# Power_Supply_1.net
KiCad netlist of a schematic drawn in Altium Designer
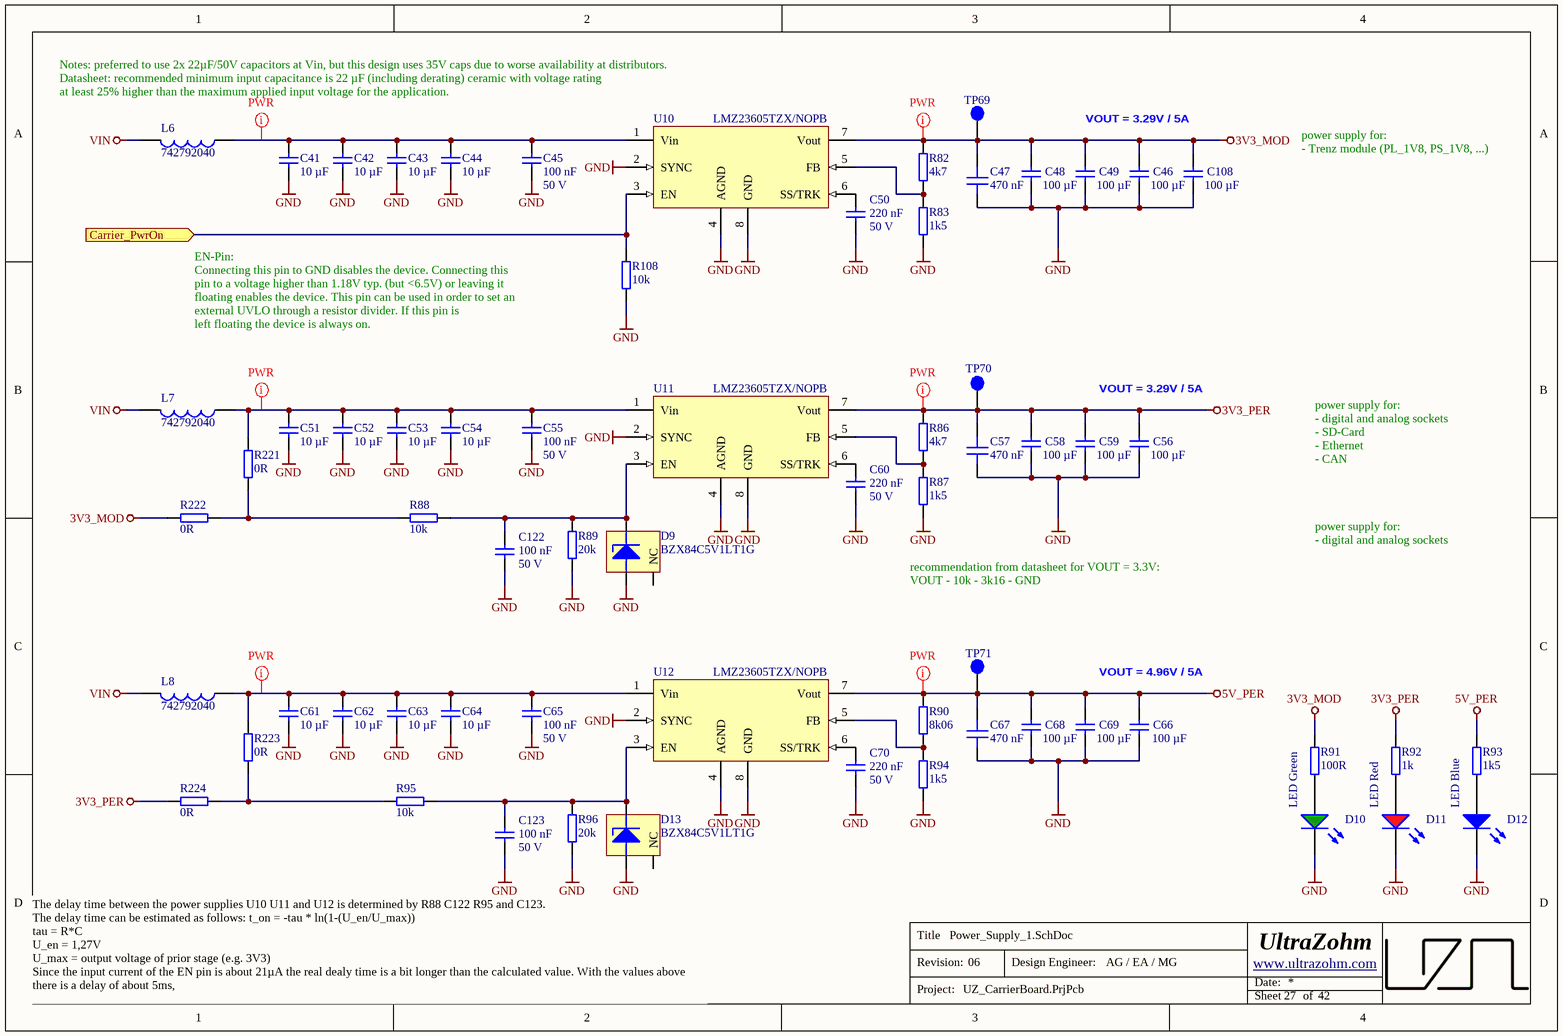
[diagram p0: Power_Supply_1.SchDoc]

(export (version "E")
  (design (tool "Eeschema 10.0.6"))
  (components
    (comp (ref "C41")
      (value "10 µF")
      (footprint "C_1206_TE")
      (description "Generic capacitor")
      (fields
        (field (name "TOLERANCE") "10 %")
        (field (name "MANUFACTURER PART NUMBER") "UZgen_C_1206_10uF_50V_X7R")
        (field (name "CREATED FROM") "MGeier")
      )
      (libsource (lib "user") (part "CAP-NP"))
    )
    (comp (ref "C42")
      (value "10 µF")
      (footprint "C_1206_TE")
      (description "Generic capacitor")
      (fields
        (field (name "TOLERANCE") "10 %")
        (field (name "MANUFACTURER PART NUMBER") "UZgen_C_1206_10uF_50V_X7R")
        (field (name "CREATED FROM") "MGeier")
      )
      (libsource (lib "user") (part "CAP-NP"))
    )
    (comp (ref "C43")
      (value "10 µF")
      (footprint "C_1206_TE")
      (description "Generic capacitor")
      (fields
        (field (name "TOLERANCE") "10 %")
        (field (name "MANUFACTURER PART NUMBER") "UZgen_C_1206_10uF_50V_X7R")
        (field (name "CREATED FROM") "MGeier")
      )
      (libsource (lib "user") (part "CAP-NP"))
    )
    (comp (ref "C44")
      (value "10 µF")
      (footprint "C_1206_TE")
      (description "Generic capacitor")
      (fields
        (field (name "TOLERANCE") "10 %")
        (field (name "MANUFACTURER PART NUMBER") "UZgen_C_1206_10uF_50V_X7R")
        (field (name "CREATED FROM") "MGeier")
      )
      (libsource (lib "user") (part "CAP-NP"))
    )
    (comp (ref "C45")
      (value "100 nF")
      (footprint "C_0603_TE")
      (description "Generic capacitor")
      (fields
        (field (name "TOLERANCE") "10 %")
        (field (name "VOLTAGE") "50 V")
        (field (name "MANUFACTURER PART NUMBER") "UZgen_C_0603_100nF_50V_X7R")
        (field (name "CREATED FROM") "AGeiger")
      )
      (libsource (lib "user") (part "CAP-NP"))
    )
    (comp (ref "C46")
      (value "100 µF")
      (footprint "C_1206_TE")
      (description "6.3V 100uF X5R ±20% 1206 Multilayer Ceramic Capacitors MLCC")
      (fields
        (field (name "TOLERANCE") "20%")
        (field (name "MANUFACTURER PART NUMBER") "CL31A107MQHNNNE")
        (field (name "CREATED FROM") "MGeier")
      )
      (libsource (lib "user") (part "CAP-NP"))
    )
    (comp (ref "C47")
      (value "470 nF")
      (footprint "C_0603_TE")
      (description "Capacitor 0603, 50 VDC, 470 nF, X5R")
      (fields
        (field (name "MANUFACTURER PART NUMBER") "CL10A474KB8NNNC")
        (field (name "MANUFACTURER") "Samsung Electro-Mechanics")
        (field (name "CREATED FROM") "AGeiger")
      )
      (libsource (lib "user") (part "Capacitor"))
    )
    (comp (ref "C48")
      (value "100 µF")
      (footprint "C_1206_TE")
      (description "6.3V 100uF X5R ±20% 1206 Multilayer Ceramic Capacitors MLCC")
      (fields
        (field (name "TOLERANCE") "20%")
        (field (name "MANUFACTURER PART NUMBER") "CL31A107MQHNNNE")
        (field (name "CREATED FROM") "MGeier")
      )
      (libsource (lib "user") (part "CAP-NP"))
    )
    (comp (ref "C49")
      (value "100 µF")
      (footprint "C_1206_TE")
      (description "6.3V 100uF X5R ±20% 1206 Multilayer Ceramic Capacitors MLCC")
      (fields
        (field (name "TOLERANCE") "20%")
        (field (name "MANUFACTURER PART NUMBER") "CL31A107MQHNNNE")
        (field (name "CREATED FROM") "MGeier")
      )
      (libsource (lib "user") (part "CAP-NP"))
    )
    (comp (ref "C50")
      (value "220 nF")
      (footprint "C_0603_TE")
      (description "Generic capacitor")
      (fields
        (field (name "TOLERANCE") "10 %")
        (field (name "VOLTAGE") "50 V")
        (field (name "MANUFACTURER PART NUMBER") "UZgen_C_0603_220nF_50V_X7R")
        (field (name "CREATED FROM") "UZgenTool")
      )
      (libsource (lib "user") (part "CAP-NP"))
    )
    (comp (ref "C51")
      (value "10 µF")
      (footprint "C_1206_TE")
      (description "Generic capacitor")
      (fields
        (field (name "TOLERANCE") "10 %")
        (field (name "MANUFACTURER PART NUMBER") "UZgen_C_1206_10uF_50V_X7R")
        (field (name "CREATED FROM") "MGeier")
      )
      (libsource (lib "user") (part "CAP-NP"))
    )
    (comp (ref "C52")
      (value "10 µF")
      (footprint "C_1206_TE")
      (description "Generic capacitor")
      (fields
        (field (name "TOLERANCE") "10 %")
        (field (name "MANUFACTURER PART NUMBER") "UZgen_C_1206_10uF_50V_X7R")
        (field (name "CREATED FROM") "MGeier")
      )
      (libsource (lib "user") (part "CAP-NP"))
    )
    (comp (ref "C53")
      (value "10 µF")
      (footprint "C_1206_TE")
      (description "Generic capacitor")
      (fields
        (field (name "TOLERANCE") "10 %")
        (field (name "MANUFACTURER PART NUMBER") "UZgen_C_1206_10uF_50V_X7R")
        (field (name "CREATED FROM") "MGeier")
      )
      (libsource (lib "user") (part "CAP-NP"))
    )
    (comp (ref "C54")
      (value "10 µF")
      (footprint "C_1206_TE")
      (description "Generic capacitor")
      (fields
        (field (name "TOLERANCE") "10 %")
        (field (name "MANUFACTURER PART NUMBER") "UZgen_C_1206_10uF_50V_X7R")
        (field (name "CREATED FROM") "MGeier")
      )
      (libsource (lib "user") (part "CAP-NP"))
    )
    (comp (ref "C55")
      (value "100 nF")
      (footprint "C_0603_TE")
      (description "Generic capacitor")
      (fields
        (field (name "TOLERANCE") "10 %")
        (field (name "VOLTAGE") "50 V")
        (field (name "MANUFACTURER PART NUMBER") "UZgen_C_0603_100nF_50V_X7R")
        (field (name "CREATED FROM") "AGeiger")
      )
      (libsource (lib "user") (part "CAP-NP"))
    )
    (comp (ref "C56")
      (value "100 µF")
      (footprint "C_1206_TE")
      (description "6.3V 100uF X5R ±20% 1206 Multilayer Ceramic Capacitors MLCC")
      (fields
        (field (name "TOLERANCE") "20%")
        (field (name "MANUFACTURER PART NUMBER") "CL31A107MQHNNNE")
        (field (name "CREATED FROM") "MGeier")
      )
      (libsource (lib "user") (part "CAP-NP"))
    )
    (comp (ref "C57")
      (value "470 nF")
      (footprint "C_0603_TE")
      (description "Capacitor 0603, 50 VDC, 470 nF, X5R")
      (fields
        (field (name "MANUFACTURER PART NUMBER") "CL10A474KB8NNNC")
        (field (name "MANUFACTURER") "Samsung Electro-Mechanics")
        (field (name "CREATED FROM") "AGeiger")
      )
      (libsource (lib "user") (part "Capacitor"))
    )
    (comp (ref "C58")
      (value "100 µF")
      (footprint "C_1206_TE")
      (description "6.3V 100uF X5R ±20% 1206 Multilayer Ceramic Capacitors MLCC")
      (fields
        (field (name "TOLERANCE") "20%")
        (field (name "MANUFACTURER PART NUMBER") "CL31A107MQHNNNE")
        (field (name "CREATED FROM") "MGeier")
      )
      (libsource (lib "user") (part "CAP-NP"))
    )
    (comp (ref "C59")
      (value "100 µF")
      (footprint "C_1206_TE")
      (description "6.3V 100uF X5R ±20% 1206 Multilayer Ceramic Capacitors MLCC")
      (fields
        (field (name "TOLERANCE") "20%")
        (field (name "MANUFACTURER PART NUMBER") "CL31A107MQHNNNE")
        (field (name "CREATED FROM") "MGeier")
      )
      (libsource (lib "user") (part "CAP-NP"))
    )
    (comp (ref "C60")
      (value "220 nF")
      (footprint "C_0603_TE")
      (description "Generic capacitor")
      (fields
        (field (name "TOLERANCE") "10 %")
        (field (name "VOLTAGE") "50 V")
        (field (name "MANUFACTURER PART NUMBER") "UZgen_C_0603_220nF_50V_X7R")
        (field (name "CREATED FROM") "UZgenTool")
      )
      (libsource (lib "user") (part "CAP-NP"))
    )
    (comp (ref "C61")
      (value "10 µF")
      (footprint "C_1206_TE")
      (description "Generic capacitor")
      (fields
        (field (name "TOLERANCE") "10 %")
        (field (name "MANUFACTURER PART NUMBER") "UZgen_C_1206_10uF_50V_X7R")
        (field (name "CREATED FROM") "MGeier")
      )
      (libsource (lib "user") (part "CAP-NP"))
    )
    (comp (ref "C62")
      (value "10 µF")
      (footprint "C_1206_TE")
      (description "Generic capacitor")
      (fields
        (field (name "TOLERANCE") "10 %")
        (field (name "MANUFACTURER PART NUMBER") "UZgen_C_1206_10uF_50V_X7R")
        (field (name "CREATED FROM") "MGeier")
      )
      (libsource (lib "user") (part "CAP-NP"))
    )
    (comp (ref "C63")
      (value "10 µF")
      (footprint "C_1206_TE")
      (description "Generic capacitor")
      (fields
        (field (name "TOLERANCE") "10 %")
        (field (name "MANUFACTURER PART NUMBER") "UZgen_C_1206_10uF_50V_X7R")
        (field (name "CREATED FROM") "MGeier")
      )
      (libsource (lib "user") (part "CAP-NP"))
    )
    (comp (ref "C64")
      (value "10 µF")
      (footprint "C_1206_TE")
      (description "Generic capacitor")
      (fields
        (field (name "TOLERANCE") "10 %")
        (field (name "MANUFACTURER PART NUMBER") "UZgen_C_1206_10uF_50V_X7R")
        (field (name "CREATED FROM") "MGeier")
      )
      (libsource (lib "user") (part "CAP-NP"))
    )
    (comp (ref "C65")
      (value "100 nF")
      (footprint "C_0603_TE")
      (description "Generic capacitor")
      (fields
        (field (name "TOLERANCE") "10 %")
        (field (name "VOLTAGE") "50 V")
        (field (name "MANUFACTURER PART NUMBER") "UZgen_C_0603_100nF_50V_X7R")
        (field (name "CREATED FROM") "AGeiger")
      )
      (libsource (lib "user") (part "CAP-NP"))
    )
    (comp (ref "C66")
      (value "100 µF")
      (footprint "C_1206_TE")
      (description "6.3V 100uF X5R ±20% 1206 Multilayer Ceramic Capacitors MLCC")
      (fields
        (field (name "TOLERANCE") "20%")
        (field (name "MANUFACTURER PART NUMBER") "CL31A107MQHNNNE")
        (field (name "CREATED FROM") "MGeier")
      )
      (libsource (lib "user") (part "CAP-NP"))
    )
    (comp (ref "C67")
      (value "470 nF")
      (footprint "C_0603_TE")
      (description "Capacitor 0603, 50 VDC, 470 nF, X5R")
      (fields
        (field (name "MANUFACTURER PART NUMBER") "CL10A474KB8NNNC")
        (field (name "MANUFACTURER") "Samsung Electro-Mechanics")
        (field (name "CREATED FROM") "AGeiger")
      )
      (libsource (lib "user") (part "Capacitor"))
    )
    (comp (ref "C68")
      (value "100 µF")
      (footprint "C_1206_TE")
      (description "6.3V 100uF X5R ±20% 1206 Multilayer Ceramic Capacitors MLCC")
      (fields
        (field (name "TOLERANCE") "20%")
        (field (name "MANUFACTURER PART NUMBER") "CL31A107MQHNNNE")
        (field (name "CREATED FROM") "MGeier")
      )
      (libsource (lib "user") (part "CAP-NP"))
    )
    (comp (ref "C69")
      (value "100 µF")
      (footprint "C_1206_TE")
      (description "6.3V 100uF X5R ±20% 1206 Multilayer Ceramic Capacitors MLCC")
      (fields
        (field (name "TOLERANCE") "20%")
        (field (name "MANUFACTURER PART NUMBER") "CL31A107MQHNNNE")
        (field (name "CREATED FROM") "MGeier")
      )
      (libsource (lib "user") (part "CAP-NP"))
    )
    (comp (ref "C70")
      (value "220 nF")
      (footprint "C_0603_TE")
      (description "Generic capacitor")
      (fields
        (field (name "TOLERANCE") "10 %")
        (field (name "VOLTAGE") "50 V")
        (field (name "MANUFACTURER PART NUMBER") "UZgen_C_0603_220nF_50V_X7R")
        (field (name "CREATED FROM") "UZgenTool")
      )
      (libsource (lib "user") (part "CAP-NP"))
    )
    (comp (ref "C108")
      (value "100 µF")
      (footprint "C_1206_TE")
      (description "6.3V 100uF X5R ±20% 1206 Multilayer Ceramic Capacitors MLCC")
      (fields
        (field (name "TOLERANCE") "20%")
        (field (name "MANUFACTURER PART NUMBER") "CL31A107MQHNNNE")
        (field (name "CREATED FROM") "MGeier")
      )
      (libsource (lib "user") (part "CAP-NP"))
    )
    (comp (ref "C122")
      (value "100 nF")
      (footprint "C_0603_TE")
      (description "Generic capacitor")
      (fields
        (field (name "TOLERANCE") "10 %")
        (field (name "VOLTAGE") "50 V")
        (field (name "MANUFACTURER PART NUMBER") "UZgen_C_0603_100nF_50V_X7R")
        (field (name "CREATED FROM") "AGeiger")
      )
      (libsource (lib "user") (part "CAP-NP"))
    )
    (comp (ref "C123")
      (value "100 nF")
      (footprint "C_0603_TE")
      (description "Generic capacitor")
      (fields
        (field (name "TOLERANCE") "10 %")
        (field (name "VOLTAGE") "50 V")
        (field (name "MANUFACTURER PART NUMBER") "UZgen_C_0603_100nF_50V_X7R")
        (field (name "CREATED FROM") "AGeiger")
      )
      (libsource (lib "user") (part "CAP-NP"))
    )
    (comp (ref "D9")
      (value "BZX84C5V1LT1G")
      (footprint "SOT95P237X112-3N")
      (description "Zener Diode 5.1V 6% 225mW")
      (fields (field (name "VOLTAGE") "5.1V"))
      (libsource (lib "TE") (part "ZENER-SOT23"))
    )
    (comp (ref "D10")
      (value "LED Green")
      (footprint "WL-SMCW_0603")
      (description "Standard LEDs - SMD 0603 green")
      (fields
        (field (name "MANUFACTURER PART NUMBER") "UZgen_LED_0603_Green")
        (field (name "MANUFACTURER") "UZgen")
        (field (name "CREATED FROM") "UZgenTool")
      )
      (libsource (lib "user") (part "LED_Green"))
    )
    (comp (ref "D11")
      (value "LED Red")
      (footprint "WL-SMCW_0603")
      (description "Standard LEDs - SMD 0603 red")
      (fields
        (field (name "MANUFACTURER PART NUMBER") "UZgen_LED_0603_Red")
        (field (name "MANUFACTURER") "UZgen")
        (field (name "CREATED FROM") "UZgenTool")
      )
      (libsource (lib "user") (part "LED_Red"))
    )
    (comp (ref "D12")
      (value "LED Blue")
      (footprint "WL-SMCW_0603")
      (description "Standard LEDs - SMD 0603 blue")
      (fields
        (field (name "MANUFACTURER PART NUMBER") "UZgen_LED_0603_Blue")
        (field (name "MANUFACTURER") "UZgen")
        (field (name "CREATED FROM") "UZgenTool")
      )
      (libsource (lib "user") (part "LED_Blue"))
    )
    (comp (ref "D13")
      (value "BZX84C5V1LT1G")
      (footprint "SOT95P237X112-3N")
      (description "Zener Diode 5.1V 6% 225mW")
      (fields (field (name "VOLTAGE") "5.1V"))
      (libsource (lib "TE") (part "ZENER-SOT23"))
    )
    (comp (ref "L6")
      (value "742792040")
      (footprint "WE-CBF_0805_High Current")
      (description "Inductance, 0805, 100 MHz, 600 Ohm, 2 A")
      (fields
        (field (name "MANUFACTURER") "Wuerth Elektronik")
        (field (name "LCSC PART NUMBER") "C2661857")
        (field (name "CREATED FROM") "AGeiger")
      )
      (libsource (lib "user") (part "WE-CBF"))
    )
    (comp (ref "L7")
      (value "742792040")
      (footprint "WE-CBF_0805_High Current")
      (description "Inductance, 0805, 100 MHz, 600 Ohm, 2 A")
      (fields
        (field (name "MANUFACTURER") "Wuerth Elektronik")
        (field (name "LCSC PART NUMBER") "C2661857")
        (field (name "CREATED FROM") "AGeiger")
      )
      (libsource (lib "user") (part "WE-CBF"))
    )
    (comp (ref "L8")
      (value "742792040")
      (footprint "WE-CBF_0805_High Current")
      (description "Inductance, 0805, 100 MHz, 600 Ohm, 2 A")
      (fields
        (field (name "MANUFACTURER") "Wuerth Elektronik")
        (field (name "LCSC PART NUMBER") "C2661857")
        (field (name "CREATED FROM") "AGeiger")
      )
      (libsource (lib "user") (part "WE-CBF"))
    )
    (comp (ref "R82")
      (value "4k7")
      (footprint "R_0603_TE")
      (description "Generic resistor")
      (fields
        (field (name "TOLERANCE") "1 %")
        (field (name "MANUFACTURER PART NUMBER") "UZgen_R_0603_4k7")
        (field (name "CREATED FROM") "UZgenTool")
      )
      (libsource (lib "user") (part "RES"))
    )
    (comp (ref "R83")
      (value "1k5")
      (footprint "R_0603_TE")
      (description "Generic resistor")
      (fields
        (field (name "TOLERANCE") "1 %")
        (field (name "MANUFACTURER PART NUMBER") "UZgen_R_0603_1k5")
        (field (name "CREATED FROM") "UZgenTool")
      )
      (libsource (lib "user") (part "RES"))
    )
    (comp (ref "R86")
      (value "4k7")
      (footprint "R_0603_TE")
      (description "Generic resistor")
      (fields
        (field (name "TOLERANCE") "1 %")
        (field (name "MANUFACTURER PART NUMBER") "UZgen_R_0603_4k7")
        (field (name "CREATED FROM") "UZgenTool")
      )
      (libsource (lib "user") (part "RES"))
    )
    (comp (ref "R87")
      (value "1k5")
      (footprint "R_0603_TE")
      (description "Generic resistor")
      (fields
        (field (name "TOLERANCE") "1 %")
        (field (name "MANUFACTURER PART NUMBER") "UZgen_R_0603_1k5")
        (field (name "CREATED FROM") "UZgenTool")
      )
      (libsource (lib "user") (part "RES"))
    )
    (comp (ref "R88")
      (value "10k")
      (footprint "R_0603_TE")
      (description "Generic resistor")
      (fields
        (field (name "TOLERANCE") "1 %")
        (field (name "MANUFACTURER PART NUMBER") "UZgen_R_0603_10k")
        (field (name "CREATED FROM") "AGeiger")
      )
      (libsource (lib "user") (part "RES"))
    )
    (comp (ref "R89")
      (value "20k")
      (footprint "R_0603_TE")
      (description "Generic resistor")
      (fields
        (field (name "TOLERANCE") "1 %")
        (field (name "MANUFACTURER PART NUMBER") "UZgen_R_0603_20k")
        (field (name "CREATED FROM") "UZgenTool")
      )
      (libsource (lib "user") (part "RES"))
    )
    (comp (ref "R90")
      (value "8k06")
      (footprint "R_0402_TE")
      (description "Non generic resistor")
      (fields
        (field (name "TOLERANCE") "1 %")
        (field (name "MANUFACTURER PART NUMBER") "UZgen_R_0402_8k06")
        (field (name "CREATED FROM") "UZgenTool")
      )
      (libsource (lib "user") (part "RES"))
    )
    (comp (ref "R91")
      (value "100R")
      (footprint "R_0603_TE")
      (description "Generic resistor")
      (fields
        (field (name "TOLERANCE") "1 %")
        (field (name "MANUFACTURER PART NUMBER") "UZgen_R_0603_100R")
        (field (name "CREATED FROM") "UZgenTool")
      )
      (libsource (lib "user") (part "RES"))
    )
    (comp (ref "R92")
      (value "1k")
      (footprint "R_0603_TE")
      (description "Generic resistor")
      (fields
        (field (name "TOLERANCE") "1 %")
        (field (name "MANUFACTURER PART NUMBER") "UZgen_R_0603_1k")
        (field (name "CREATED FROM") "UZgenTool")
      )
      (libsource (lib "user") (part "RES"))
    )
    (comp (ref "R93")
      (value "1k5")
      (footprint "R_0603_TE")
      (description "Generic resistor")
      (fields
        (field (name "TOLERANCE") "1 %")
        (field (name "MANUFACTURER PART NUMBER") "UZgen_R_0603_1k5")
        (field (name "CREATED FROM") "UZgenTool")
      )
      (libsource (lib "user") (part "RES"))
    )
    (comp (ref "R94")
      (value "1k5")
      (footprint "R_0603_TE")
      (description "Generic resistor")
      (fields
        (field (name "TOLERANCE") "1 %")
        (field (name "MANUFACTURER PART NUMBER") "UZgen_R_0603_1k5")
        (field (name "CREATED FROM") "UZgenTool")
      )
      (libsource (lib "user") (part "RES"))
    )
    (comp (ref "R95")
      (value "10k")
      (footprint "R_0603_TE")
      (description "Generic resistor")
      (fields
        (field (name "TOLERANCE") "1 %")
        (field (name "MANUFACTURER PART NUMBER") "UZgen_R_0603_10k")
        (field (name "CREATED FROM") "AGeiger")
      )
      (libsource (lib "user") (part "RES"))
    )
    (comp (ref "R96")
      (value "20k")
      (footprint "R_0603_TE")
      (description "Generic resistor")
      (fields
        (field (name "TOLERANCE") "1 %")
        (field (name "MANUFACTURER PART NUMBER") "UZgen_R_0603_20k")
        (field (name "CREATED FROM") "UZgenTool")
      )
      (libsource (lib "user") (part "RES"))
    )
    (comp (ref "R108")
      (value "10k")
      (footprint "R_0603_TE")
      (description "Generic resistor")
      (fields
        (field (name "MANUFACTURER PART NUMBER") "UZgen_R_0603_10k")
        (field (name "MANUFACTURER") "UZgen")
        (field (name "CREATED FROM") "AGeiger")
      )
      (libsource (lib "user") (part "RES"))
    )
    (comp (ref "R221")
      (value "0R")
      (footprint "R_1206_TE")
      (description "Generic resistor")
      (fields
        (field (name "TOLERANCE") "1 %")
        (field (name "MANUFACTURER PART NUMBER") "UZgen_R_1206_0R")
        (field (name "CREATED FROM") "UZgenTool")
      )
      (libsource (lib "user") (part "RES"))
    )
    (comp (ref "R222")
      (value "0R")
      (footprint "R_1206_TE")
      (description "Generic resistor")
      (fields
        (field (name "TOLERANCE") "1 %")
        (field (name "MANUFACTURER PART NUMBER") "UZgen_R_1206_0R")
        (field (name "CREATED FROM") "UZgenTool")
      )
      (libsource (lib "user") (part "RES"))
    )
    (comp (ref "R223")
      (value "0R")
      (footprint "R_1206_TE")
      (description "Generic resistor")
      (fields
        (field (name "TOLERANCE") "1 %")
        (field (name "MANUFACTURER PART NUMBER") "UZgen_R_1206_0R")
        (field (name "CREATED FROM") "UZgenTool")
      )
      (libsource (lib "user") (part "RES"))
    )
    (comp (ref "R224")
      (value "0R")
      (footprint "R_1206_TE")
      (description "Generic resistor")
      (fields
        (field (name "TOLERANCE") "1 %")
        (field (name "MANUFACTURER PART NUMBER") "UZgen_R_1206_0R")
        (field (name "CREATED FROM") "UZgenTool")
      )
      (libsource (lib "user") (part "RES"))
    )
    (comp (ref "TP69") (value "Testpoint 1mm") (footprint "TP_1mm") (libsource (lib "TE") (part "TP")))
    (comp (ref "TP70") (value "Testpoint 1mm") (footprint "TP_1mm") (libsource (lib "TE") (part "TP")))
    (comp (ref "TP71") (value "Testpoint 1mm") (footprint "TP_1mm") (libsource (lib "TE") (part "TP")))
    (comp (ref "U10")
      (value "LMZ23605TZX/NOPB")
      (footprint "7TO-PMOD")
      (description "Switching Voltage Regulators Gen2 36Vin 5A Module")
      (fields
        (field (name "MANUFACTURER") "Texas Instruments")
        (field (name "LCSC PART NUMBER") "C913851")
        (field (name "CREATED FROM") "FRosner")
      )
      (libsource (lib "user") (part "LMZ23605TZ"))
    )
    (comp (ref "U11")
      (value "LMZ23605TZX/NOPB")
      (footprint "7TO-PMOD")
      (description "Switching Voltage Regulators Gen2 36Vin 5A Module")
      (fields
        (field (name "MANUFACTURER") "Texas Instruments")
        (field (name "LCSC PART NUMBER") "C913851")
        (field (name "CREATED FROM") "FRosner")
      )
      (libsource (lib "user") (part "LMZ23605TZ"))
    )
    (comp (ref "U12")
      (value "LMZ23605TZX/NOPB")
      (footprint "7TO-PMOD")
      (description "Switching Voltage Regulators Gen2 36Vin 5A Module")
      (fields
        (field (name "MANUFACTURER") "Texas Instruments")
        (field (name "LCSC PART NUMBER") "C913851")
        (field (name "CREATED FROM") "FRosner")
      )
      (libsource (lib "user") (part "LMZ23605TZ"))
    )
  )
  (nets
    (net (code "1") (name "/Carrier_PwrOn") (class "Default")
      (node (ref "R108") (pin "2") (pinfunction "2_2") (pintype "passive"))
      (node (ref "U10") (pin "3") (pinfunction "EN_3") (pintype "input"))
    )
    (net (code "2") (name "3V3_MOD") (class "Default")
      (node (ref "C108") (pin "1") (pinfunction "1_1") (pintype "passive"))
      (node (ref "C46") (pin "1") (pinfunction "1_1") (pintype "passive"))
      (node (ref "C47") (pin "1") (pinfunction "1_1") (pintype "passive"))
      (node (ref "C48") (pin "1") (pinfunction "1_1") (pintype "passive"))
      (node (ref "C49") (pin "1") (pinfunction "1_1") (pintype "passive"))
      (node (ref "R222") (pin "2") (pinfunction "2_2") (pintype "passive"))
      (node (ref "R82") (pin "2") (pinfunction "2_2") (pintype "passive"))
      (node (ref "R91") (pin "2") (pinfunction "2_2") (pintype "passive"))
      (node (ref "TP69") (pin "1") (pintype "passive"))
      (node (ref "U10") (pin "7") (pinfunction "Vout_7") (pintype "power_in"))
    )
    (net (code "3") (name "3V3_PER") (class "Default")
      (node (ref "C56") (pin "1") (pinfunction "1_1") (pintype "passive"))
      (node (ref "C57") (pin "1") (pinfunction "1_1") (pintype "passive"))
      (node (ref "C58") (pin "1") (pinfunction "1_1") (pintype "passive"))
      (node (ref "C59") (pin "1") (pinfunction "1_1") (pintype "passive"))
      (node (ref "R224") (pin "2") (pinfunction "2_2") (pintype "passive"))
      (node (ref "R86") (pin "2") (pinfunction "2_2") (pintype "passive"))
      (node (ref "R92") (pin "2") (pinfunction "2_2") (pintype "passive"))
      (node (ref "TP70") (pin "1") (pintype "passive"))
      (node (ref "U11") (pin "7") (pinfunction "Vout_7") (pintype "power_in"))
    )
    (net (code "4") (name "5V_PER") (class "Default")
      (node (ref "C66") (pin "1") (pinfunction "1_1") (pintype "passive"))
      (node (ref "C67") (pin "1") (pinfunction "1_1") (pintype "passive"))
      (node (ref "C68") (pin "1") (pinfunction "1_1") (pintype "passive"))
      (node (ref "C69") (pin "1") (pinfunction "1_1") (pintype "passive"))
      (node (ref "R90") (pin "1") (pinfunction "1_1") (pintype "passive"))
      (node (ref "R93") (pin "2") (pinfunction "2_2") (pintype "passive"))
      (node (ref "TP71") (pin "1") (pintype "passive"))
      (node (ref "U12") (pin "7") (pinfunction "Vout_7") (pintype "power_in"))
    )
    (net (code "5") (name "GND") (class "Default")
      (node (ref "C108") (pin "2") (pinfunction "2_2") (pintype "passive"))
      (node (ref "C122") (pin "2") (pinfunction "2_2") (pintype "passive"))
      (node (ref "C123") (pin "2") (pinfunction "2_2") (pintype "passive"))
      (node (ref "C41") (pin "2") (pinfunction "2_2") (pintype "passive"))
      (node (ref "C42") (pin "2") (pinfunction "2_2") (pintype "passive"))
      (node (ref "C43") (pin "2") (pinfunction "2_2") (pintype "passive"))
      (node (ref "C44") (pin "2") (pinfunction "2_2") (pintype "passive"))
      (node (ref "C45") (pin "1") (pinfunction "1_1") (pintype "passive"))
      (node (ref "C46") (pin "2") (pinfunction "2_2") (pintype "passive"))
      (node (ref "C47") (pin "2") (pinfunction "2_2") (pintype "passive"))
      (node (ref "C48") (pin "2") (pinfunction "2_2") (pintype "passive"))
      (node (ref "C49") (pin "2") (pinfunction "2_2") (pintype "passive"))
      (node (ref "C50") (pin "2") (pinfunction "2_2") (pintype "passive"))
      (node (ref "C51") (pin "2") (pinfunction "2_2") (pintype "passive"))
      (node (ref "C52") (pin "2") (pinfunction "2_2") (pintype "passive"))
      (node (ref "C53") (pin "2") (pinfunction "2_2") (pintype "passive"))
      (node (ref "C54") (pin "2") (pinfunction "2_2") (pintype "passive"))
      (node (ref "C55") (pin "1") (pinfunction "1_1") (pintype "passive"))
      (node (ref "C56") (pin "2") (pinfunction "2_2") (pintype "passive"))
      (node (ref "C57") (pin "2") (pinfunction "2_2") (pintype "passive"))
      (node (ref "C58") (pin "2") (pinfunction "2_2") (pintype "passive"))
      (node (ref "C59") (pin "2") (pinfunction "2_2") (pintype "passive"))
      (node (ref "C60") (pin "2") (pinfunction "2_2") (pintype "passive"))
      (node (ref "C61") (pin "2") (pinfunction "2_2") (pintype "passive"))
      (node (ref "C62") (pin "2") (pinfunction "2_2") (pintype "passive"))
      (node (ref "C63") (pin "2") (pinfunction "2_2") (pintype "passive"))
      (node (ref "C64") (pin "2") (pinfunction "2_2") (pintype "passive"))
      (node (ref "C65") (pin "1") (pinfunction "1_1") (pintype "passive"))
      (node (ref "C66") (pin "2") (pinfunction "2_2") (pintype "passive"))
      (node (ref "C67") (pin "2") (pinfunction "2_2") (pintype "passive"))
      (node (ref "C68") (pin "2") (pinfunction "2_2") (pintype "passive"))
      (node (ref "C69") (pin "2") (pinfunction "2_2") (pintype "passive"))
      (node (ref "C70") (pin "2") (pinfunction "2_2") (pintype "passive"))
      (node (ref "D10") (pin "1") (pinfunction "K_1") (pintype "passive"))
      (node (ref "D11") (pin "1") (pinfunction "K_1") (pintype "passive"))
      (node (ref "D12") (pin "1") (pinfunction "K_1") (pintype "passive"))
      (node (ref "D13") (pin "1") (pinfunction "ANODE_1") (pintype "passive"))
      (node (ref "D9") (pin "1") (pinfunction "ANODE_1") (pintype "passive"))
      (node (ref "R108") (pin "1") (pinfunction "1_1") (pintype "passive"))
      (node (ref "R83") (pin "1") (pinfunction "1_1") (pintype "passive"))
      (node (ref "R87") (pin "1") (pinfunction "1_1") (pintype "passive"))
      (node (ref "R89") (pin "1") (pinfunction "1_1") (pintype "passive"))
      (node (ref "R94") (pin "2") (pinfunction "2_2") (pintype "passive"))
      (node (ref "R96") (pin "1") (pinfunction "1_1") (pintype "passive"))
      (node (ref "U10") (pin "2") (pinfunction "SYNC_2") (pintype "input"))
      (node (ref "U10") (pin "4") (pinfunction "AGND_4") (pintype "power_in"))
      (node (ref "U10") (pin "8") (pinfunction "GND_8") (pintype "power_in"))
      (node (ref "U11") (pin "2") (pinfunction "SYNC_2") (pintype "input"))
      (node (ref "U11") (pin "4") (pinfunction "AGND_4") (pintype "power_in"))
      (node (ref "U11") (pin "8") (pinfunction "GND_8") (pintype "power_in"))
      (node (ref "U12") (pin "2") (pinfunction "SYNC_2") (pintype "input"))
      (node (ref "U12") (pin "4") (pinfunction "AGND_4") (pintype "power_in"))
      (node (ref "U12") (pin "8") (pinfunction "GND_8") (pintype "power_in"))
    )
    (net (code "6") (name "Net-(D9-KATHODE)") (class "Default")
      (node (ref "C122") (pin "1") (pinfunction "1_1") (pintype "passive"))
      (node (ref "D9") (pin "3") (pinfunction "KATHODE_3") (pintype "passive"))
      (node (ref "R88") (pin "2") (pinfunction "2_2") (pintype "passive"))
      (node (ref "R89") (pin "2") (pinfunction "2_2") (pintype "passive"))
      (node (ref "U11") (pin "3") (pinfunction "EN_3") (pintype "input"))
    )
    (net (code "7") (name "Net-(D10-A)") (class "Default")
      (node (ref "D10") (pin "2") (pinfunction "A_2") (pintype "passive"))
      (node (ref "R91") (pin "1") (pinfunction "1_1") (pintype "passive"))
    )
    (net (code "8") (name "Net-(D11-A)") (class "Default")
      (node (ref "D11") (pin "2") (pinfunction "A_2") (pintype "passive"))
      (node (ref "R92") (pin "1") (pinfunction "1_1") (pintype "passive"))
    )
    (net (code "9") (name "Net-(D12-A)") (class "Default")
      (node (ref "D12") (pin "2") (pinfunction "A_2") (pintype "passive"))
      (node (ref "R93") (pin "1") (pinfunction "1_1") (pintype "passive"))
    )
    (net (code "10") (name "Net-(D13-KATHODE)") (class "Default")
      (node (ref "C123") (pin "1") (pinfunction "1_1") (pintype "passive"))
      (node (ref "D13") (pin "3") (pinfunction "KATHODE_3") (pintype "passive"))
      (node (ref "R95") (pin "2") (pinfunction "2_2") (pintype "passive"))
      (node (ref "R96") (pin "2") (pinfunction "2_2") (pintype "passive"))
      (node (ref "U12") (pin "3") (pinfunction "EN_3") (pintype "input"))
    )
    (net (code "11") (name "Net-(R221-Pad1)") (class "Default")
      (node (ref "R221") (pin "1") (pinfunction "1_1") (pintype "passive"))
      (node (ref "R222") (pin "1") (pinfunction "1_1") (pintype "passive"))
      (node (ref "R88") (pin "1") (pinfunction "1_1") (pintype "passive"))
    )
    (net (code "12") (name "Net-(R223-Pad1)") (class "Default")
      (node (ref "R223") (pin "1") (pinfunction "1_1") (pintype "passive"))
      (node (ref "R224") (pin "1") (pinfunction "1_1") (pintype "passive"))
      (node (ref "R95") (pin "1") (pinfunction "1_1") (pintype "passive"))
    )
    (net (code "13") (name "Net-(U10-FB)") (class "Default")
      (node (ref "R82") (pin "1") (pinfunction "1_1") (pintype "passive"))
      (node (ref "R83") (pin "2") (pinfunction "2_2") (pintype "passive"))
      (node (ref "U10") (pin "5") (pinfunction "FB_5") (pintype "input"))
    )
    (net (code "14") (name "Net-(U10-SS{slash}TRK)") (class "Default")
      (node (ref "C50") (pin "1") (pinfunction "1_1") (pintype "passive"))
      (node (ref "U10") (pin "6") (pinfunction "SS/TRK_6") (pintype "input"))
    )
    (net (code "15") (name "Net-(U10-Vin)") (class "Default")
      (node (ref "C41") (pin "1") (pinfunction "1_1") (pintype "passive"))
      (node (ref "C42") (pin "1") (pinfunction "1_1") (pintype "passive"))
      (node (ref "C43") (pin "1") (pinfunction "1_1") (pintype "passive"))
      (node (ref "C44") (pin "1") (pinfunction "1_1") (pintype "passive"))
      (node (ref "C45") (pin "2") (pinfunction "2_2") (pintype "passive"))
      (node (ref "L6") (pin "1") (pinfunction "1_1") (pintype "passive"))
      (node (ref "U10") (pin "1") (pinfunction "Vin_1") (pintype "power_in"))
    )
    (net (code "16") (name "Net-(U11-FB)") (class "Default")
      (node (ref "R86") (pin "1") (pinfunction "1_1") (pintype "passive"))
      (node (ref "R87") (pin "2") (pinfunction "2_2") (pintype "passive"))
      (node (ref "U11") (pin "5") (pinfunction "FB_5") (pintype "input"))
    )
    (net (code "17") (name "Net-(U11-SS{slash}TRK)") (class "Default")
      (node (ref "C60") (pin "1") (pinfunction "1_1") (pintype "passive"))
      (node (ref "U11") (pin "6") (pinfunction "SS/TRK_6") (pintype "input"))
    )
    (net (code "18") (name "Net-(U11-Vin)") (class "Default")
      (node (ref "C51") (pin "1") (pinfunction "1_1") (pintype "passive"))
      (node (ref "C52") (pin "1") (pinfunction "1_1") (pintype "passive"))
      (node (ref "C53") (pin "1") (pinfunction "1_1") (pintype "passive"))
      (node (ref "C54") (pin "1") (pinfunction "1_1") (pintype "passive"))
      (node (ref "C55") (pin "2") (pinfunction "2_2") (pintype "passive"))
      (node (ref "L7") (pin "1") (pinfunction "1_1") (pintype "passive"))
      (node (ref "R221") (pin "2") (pinfunction "2_2") (pintype "passive"))
      (node (ref "U11") (pin "1") (pinfunction "Vin_1") (pintype "power_in"))
    )
    (net (code "19") (name "Net-(U12-FB)") (class "Default")
      (node (ref "R90") (pin "2") (pinfunction "2_2") (pintype "passive"))
      (node (ref "R94") (pin "1") (pinfunction "1_1") (pintype "passive"))
      (node (ref "U12") (pin "5") (pinfunction "FB_5") (pintype "input"))
    )
    (net (code "20") (name "Net-(U12-SS{slash}TRK)") (class "Default")
      (node (ref "C70") (pin "1") (pinfunction "1_1") (pintype "passive"))
      (node (ref "U12") (pin "6") (pinfunction "SS/TRK_6") (pintype "input"))
    )
    (net (code "21") (name "Net-(U12-Vin)") (class "Default")
      (node (ref "C61") (pin "1") (pinfunction "1_1") (pintype "passive"))
      (node (ref "C62") (pin "1") (pinfunction "1_1") (pintype "passive"))
      (node (ref "C63") (pin "1") (pinfunction "1_1") (pintype "passive"))
      (node (ref "C64") (pin "1") (pinfunction "1_1") (pintype "passive"))
      (node (ref "C65") (pin "2") (pinfunction "2_2") (pintype "passive"))
      (node (ref "L8") (pin "1") (pinfunction "1_1") (pintype "passive"))
      (node (ref "R223") (pin "2") (pinfunction "2_2") (pintype "passive"))
      (node (ref "U12") (pin "1") (pinfunction "Vin_1") (pintype "power_in"))
    )
    (net (code "22") (name "VIN") (class "Default")
      (node (ref "L6") (pin "2") (pinfunction "2_2") (pintype "passive"))
      (node (ref "L7") (pin "2") (pinfunction "2_2") (pintype "passive"))
      (node (ref "L8") (pin "2") (pinfunction "2_2") (pintype "passive"))
    )
    (net (code "23") (name "unconnected-(D9-NC-Pad2)") (class "Default")
      (node (ref "D9") (pin "2") (pinfunction "NC_2") (pintype "power_in"))
    )
    (net (code "24") (name "unconnected-(D13-NC-Pad2)") (class "Default")
      (node (ref "D13") (pin "2") (pinfunction "NC_2") (pintype "power_in"))
    )
  )
)
